# Mako_DSP_Power_R2_0.net
KiCad netlist of a schematic drawn in Altium Designer
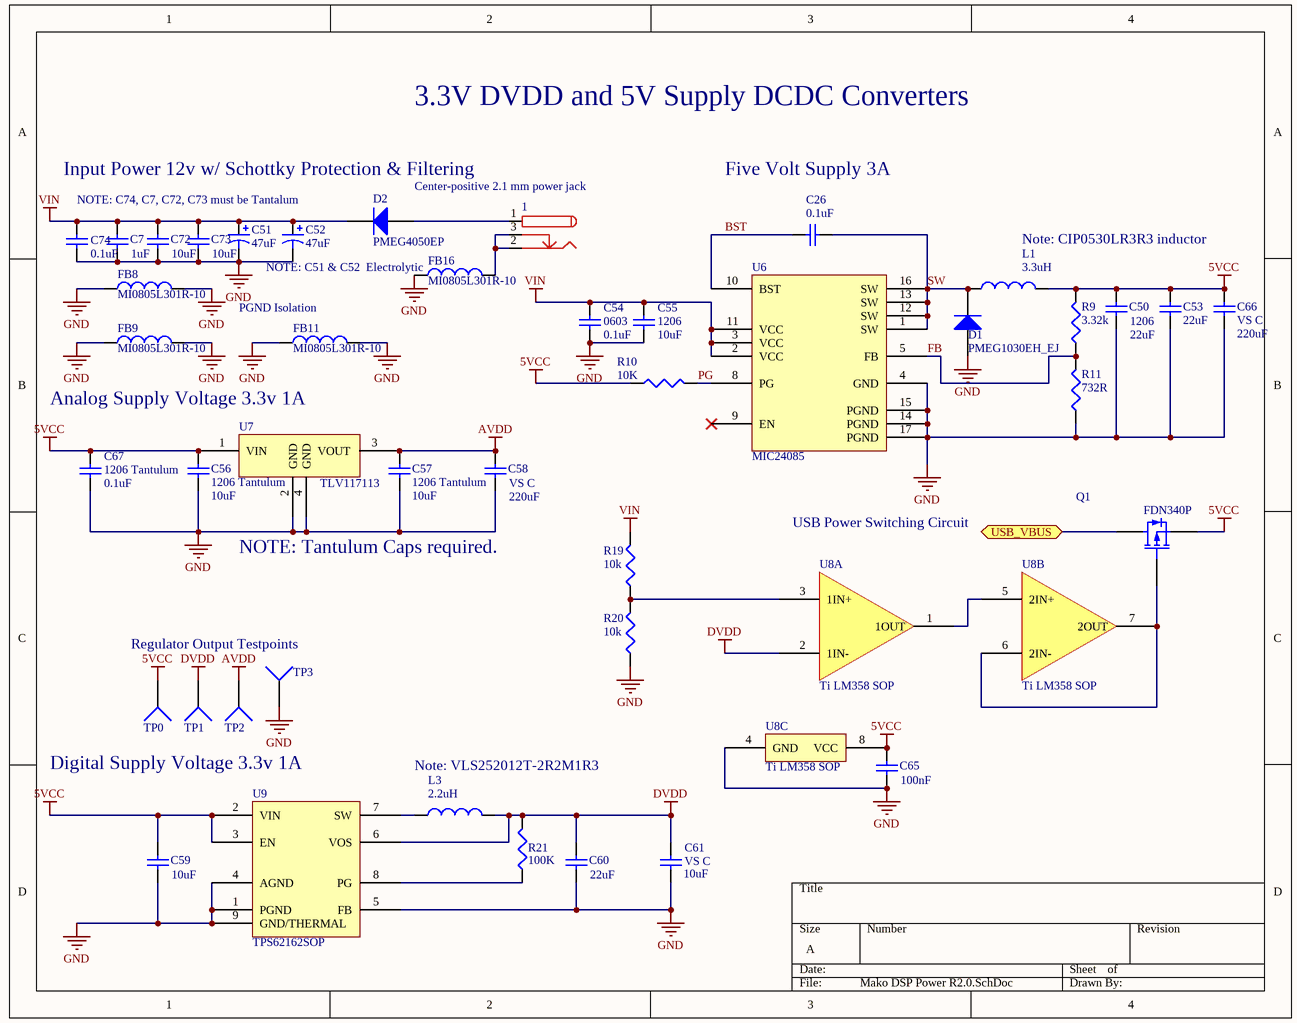
[diagram p0: Mako DSP Power R2.0.SchDoc]

(export (version "E")
  (design (tool "Eeschema 10.0.6"))
  (components
    (comp (ref "1")
      (value "Center-positive 2.1 mm power jack")
      (footprint "PJ-102AH")
      (description "Power jack")
      (fields (field (name "PUBLISHER") "Altium Limited"))
      (libsource (lib "Rascal") (part "PWR2.5"))
    )
    (comp (ref "C7")
      (value "1uF")
      (footprint "C1206")
      (description "Capacitor (Semiconductor SIM Model)")
      (fields (field (name "Comment") "Cap Semi") (field (name "PUBLISHER") "Altium Limited"))
      (libsource (lib "Miscellaneous Devices") (part "Cap Semi"))
    )
    (comp (ref "C26")
      (value "0.1uF")
      (footprint "1608[0603]")
      (description "Capacitor (Semiconductor SIM Model)")
      (fields (field (name "Comment") "Cap Semi") (field (name "PUBLISHER") "Altium Limited"))
      (libsource (lib "Miscellaneous Devices") (part "Cap Semi"))
    )
    (comp (ref "C50")
      (value "1206")
      (footprint "C1206")
      (description "Capacitor (Semiconductor SIM Model)")
      (fields (field (name "ALTIUM_VALUE") "22uF") (field (name "PUBLISHER") "Altium Limited"))
      (libsource (lib "Miscellaneous Devices") (part "Cap Semi"))
    )
    (comp (ref "C51")
      (value "47uF")
      (footprint "CAPPR2.5-6.3x5")
      (description "Polarized Capacitor (Radial)")
      (fields (field (name "Comment") "Cap Pol1") (field (name "PUBLISHER") "Altium Limited"))
      (libsource (lib "Miscellaneous Devices") (part "Cap Pol1"))
    )
    (comp (ref "C52")
      (value "47uF")
      (footprint "CAPPR2.5-6.3x5")
      (description "Polarized Capacitor (Radial)")
      (fields (field (name "Comment") "Cap Pol1") (field (name "PUBLISHER") "Altium Limited"))
      (libsource (lib "Miscellaneous Devices") (part "Cap Pol1"))
    )
    (comp (ref "C53")
      (value "22uF")
      (footprint "C1206")
      (description "Capacitor (Semiconductor SIM Model)")
      (fields (field (name "Comment") "Cap Semi") (field (name "PUBLISHER") "Altium Limited"))
      (libsource (lib "Miscellaneous Devices") (part "Cap Semi"))
    )
    (comp (ref "C54")
      (value "0603")
      (footprint "1608[0603]")
      (description "Capacitor (Semiconductor SIM Model)")
      (fields (field (name "ALTIUM_VALUE") "0.1uF") (field (name "PUBLISHER") "Altium Limited"))
      (libsource (lib "Miscellaneous Devices") (part "Cap Semi"))
    )
    (comp (ref "C55")
      (value "1206")
      (footprint "C1206")
      (description "Capacitor (Semiconductor SIM Model)")
      (fields (field (name "ALTIUM_VALUE") "10uF") (field (name "PUBLISHER") "Altium Limited"))
      (libsource (lib "Miscellaneous Devices") (part "Cap Semi"))
    )
    (comp (ref "C56")
      (value "1206 Tantulum")
      (footprint "C1206")
      (description "Capacitor (Semiconductor SIM Model)")
      (fields (field (name "ALTIUM_VALUE") "10uF") (field (name "PUBLISHER") "Altium Limited"))
      (libsource (lib "Miscellaneous Devices") (part "Cap Semi"))
    )
    (comp (ref "C57")
      (value "1206 Tantulum")
      (footprint "C1206")
      (description "Capacitor (Semiconductor SIM Model)")
      (fields (field (name "ALTIUM_VALUE") "10uF") (field (name "PUBLISHER") "Altium Limited"))
      (libsource (lib "Miscellaneous Devices") (part "Cap Semi"))
    )
    (comp (ref "C58")
      (value "VS C")
      (footprint "Panasonic VS C")
      (description "Capacitor (Semiconductor SIM Model)")
      (fields (field (name "ALTIUM_VALUE") "220uF") (field (name "PUBLISHER") "Altium Limited"))
      (libsource (lib "Miscellaneous Devices") (part "Cap Semi"))
    )
    (comp (ref "C59")
      (value "10uF")
      (footprint "C1206")
      (description "Capacitor (Semiconductor SIM Model)")
      (fields (field (name "Comment") "Cap Semi") (field (name "PUBLISHER") "Altium Limited"))
      (libsource (lib "Miscellaneous Devices") (part "Cap Semi"))
    )
    (comp (ref "C60")
      (value "22uF")
      (footprint "C1206")
      (description "Capacitor (Semiconductor SIM Model)")
      (fields (field (name "Comment") "Cap Semi") (field (name "PUBLISHER") "Altium Limited"))
      (libsource (lib "Miscellaneous Devices") (part "Cap Semi"))
    )
    (comp (ref "C61")
      (value "VS C")
      (footprint "Panasonic VS C")
      (description "Capacitor (Semiconductor SIM Model)")
      (fields (field (name "ALTIUM_VALUE") "10uF") (field (name "PUBLISHER") "Altium Limited"))
      (libsource (lib "Miscellaneous Devices") (part "Cap Semi"))
    )
    (comp (ref "C65")
      (value "100nF")
      (footprint "1608[0603]")
      (description "Capacitor (Semiconductor SIM Model)")
      (fields (field (name "Comment") "Cap Semi") (field (name "PUBLISHER") "Altium Limited"))
      (libsource (lib "Miscellaneous Devices") (part "Cap Semi"))
    )
    (comp (ref "C66")
      (value "VS C")
      (footprint "Panasonic VS C")
      (description "Capacitor (Semiconductor SIM Model)")
      (fields (field (name "ALTIUM_VALUE") "220uF") (field (name "PUBLISHER") "Altium Limited"))
      (libsource (lib "Miscellaneous Devices") (part "Cap Semi"))
    )
    (comp (ref "C67")
      (value "1206 Tantulum")
      (footprint "C1206")
      (description "Capacitor (Semiconductor SIM Model)")
      (fields (field (name "ALTIUM_VALUE") "0.1uF") (field (name "PUBLISHER") "Altium Limited"))
      (libsource (lib "Miscellaneous Devices") (part "Cap Semi"))
    )
    (comp (ref "C72")
      (value "10uF")
      (footprint "C1206")
      (description "Capacitor (Semiconductor SIM Model)")
      (fields (field (name "Comment") "Cap Semi") (field (name "PUBLISHER") "Altium Limited"))
      (libsource (lib "Miscellaneous Devices") (part "Cap Semi"))
    )
    (comp (ref "C73")
      (value "10uF")
      (footprint "C1206")
      (description "Capacitor (Semiconductor SIM Model)")
      (fields (field (name "Comment") "Cap Semi") (field (name "PUBLISHER") "Altium Limited"))
      (libsource (lib "Miscellaneous Devices") (part "Cap Semi"))
    )
    (comp (ref "C74")
      (value "0.1uF")
      (footprint "C1206")
      (description "Capacitor (Semiconductor SIM Model)")
      (fields (field (name "Comment") "Cap Semi") (field (name "PUBLISHER") "Altium Limited"))
      (libsource (lib "Miscellaneous Devices") (part "Cap Semi"))
    )
    (comp (ref "D1")
      (value "PMEG1030EH_EJ")
      (footprint "PMEG1030EH_EJ")
      (description "Default Diode")
      (fields (field (name "PUBLISHER") "Altium Limited"))
      (libsource (lib "") (part "Diode_1"))
    )
    (comp (ref "D2")
      (value "PMEG4050EP")
      (footprint "PMEG4050EP")
      (description "Default Diode")
      (fields (field (name "PUBLISHER") "Altium Limited"))
      (libsource (lib "Miscellaneous Devices") (part "Diode"))
    )
    (comp (ref "FB8")
      (value "MI0805L301R-10")
      (footprint "SM 0805 - gap trimmed")
      (description "Inductor")
      (fields (field (name "PUBLISHER") "Altium Limited"))
      (libsource (lib "Miscellaneous Devices") (part "Inductor"))
    )
    (comp (ref "FB9")
      (value "MI0805L301R-10")
      (footprint "SM 0805 - gap trimmed")
      (description "Inductor")
      (fields (field (name "PUBLISHER") "Altium Limited"))
      (libsource (lib "Miscellaneous Devices") (part "Inductor"))
    )
    (comp (ref "FB11")
      (value "MI0805L301R-10")
      (footprint "SM 0805 - gap trimmed")
      (description "Inductor")
      (fields (field (name "PUBLISHER") "Altium Limited"))
      (libsource (lib "Miscellaneous Devices") (part "Inductor"))
    )
    (comp (ref "FB16")
      (value "MI0805L301R-10")
      (footprint "SM 0805 - gap trimmed")
      (description "Inductor")
      (fields (field (name "PUBLISHER") "Altium Limited"))
      (libsource (lib "Miscellaneous Devices") (part "Inductor"))
    )
    (comp (ref "L1")
      (value "3.3uH")
      (footprint "CIP0530LR3R3")
      (description "Inductor")
      (fields (field (name "PUBLISHER") "Altium Limited"))
      (libsource (lib "Miscellaneous Devices") (part "Inductor"))
    )
    (comp (ref "L3")
      (value "2.2uH")
      (footprint "VLS252012T-2R2M1R3")
      (description "Inductor")
      (fields (field (name "PUBLISHER") "Altium Limited"))
      (libsource (lib "Miscellaneous Devices") (part "Inductor"))
    )
    (comp (ref "Q1")
      (value "FDN340P")
      (footprint "SOT23-3N")
      (description "P-Channel MOSFET")
      (fields (field (name "PUBLISHER") "Altium Limited"))
      (libsource (lib "Mako DSP Schematic Library") (part "FDN340P"))
    )
    (comp (ref "R9")
      (value "3.32k")
      (footprint "J1-0603")
      (description "Resistor")
      (fields (field (name "Comment") "Res3") (field (name "PUBLISHER") "Altium Limited"))
      (libsource (lib "Miscellaneous Devices") (part "Res3"))
    )
    (comp (ref "R10")
      (value "10K")
      (footprint "J1-0603")
      (description "Resistor")
      (fields (field (name "Comment") "Res3") (field (name "PUBLISHER") "Altium Limited"))
      (libsource (lib "Miscellaneous Devices") (part "Res3"))
    )
    (comp (ref "R11")
      (value "732R")
      (footprint "J1-0603")
      (description "Resistor")
      (fields (field (name "Comment") "Res3") (field (name "PUBLISHER") "Altium Limited"))
      (libsource (lib "Miscellaneous Devices") (part "Res3"))
    )
    (comp (ref "R19")
      (value "10k")
      (footprint "J1-0603")
      (description "Resistor")
      (fields (field (name "Comment") "Res3") (field (name "PUBLISHER") "Altium Limited"))
      (libsource (lib "Miscellaneous Devices") (part "Res3"))
    )
    (comp (ref "R20")
      (value "10k")
      (footprint "J1-0603")
      (description "Resistor")
      (fields (field (name "Comment") "Res3") (field (name "PUBLISHER") "Altium Limited"))
      (libsource (lib "Miscellaneous Devices") (part "Res3"))
    )
    (comp (ref "R21")
      (value "100K")
      (footprint "RESC2012L")
      (description "Resistor")
      (fields (field (name "Comment") "Res3") (field (name "PUBLISHER") "Altium Limited"))
      (libsource (lib "Miscellaneous Devices") (part "Res3"))
    )
    (comp (ref "TP0")
      (value "Socket")
      (footprint "PIN1")
      (fields (field (name "PUBLISHER") "Altium Limited"))
      (libsource (lib "Miscellaneous Connectors") (part "Socket"))
    )
    (comp (ref "TP1")
      (value "Socket")
      (footprint "PIN1")
      (fields (field (name "PUBLISHER") "Altium Limited"))
      (libsource (lib "Miscellaneous Connectors") (part "Socket"))
    )
    (comp (ref "TP2")
      (value "Socket")
      (footprint "PIN1")
      (fields (field (name "PUBLISHER") "Altium Limited"))
      (libsource (lib "Miscellaneous Connectors") (part "Socket"))
    )
    (comp (ref "TP3")
      (value "Socket")
      (footprint "PIN1")
      (fields (field (name "PUBLISHER") "Altium Limited"))
      (libsource (lib "Miscellaneous Connectors") (part "Socket"))
    )
    (comp (ref "U6")
      (value "MIC24085")
      (footprint "MIC24085-AYML")
      (libsource (lib "Adams Altium Library") (part "MIC24085"))
    )
    (comp (ref "U7")
      (value "TLV117113")
      (footprint "TLV117112")
      (description "Linear Regulator")
      (libsource (lib "Adams Altium Library") (part "TLV117112"))
    )
    (comp (ref "U8")
      (value "Ti LM358 SOP")
      (footprint "LM358")
      (libsource (lib "Mako DSP Schematic Library") (part "LM358_Symbol"))
    )
    (comp (ref "U9")
      (value "TPS62162SOP")
      (footprint "TPS62162SOP")
      (libsource (lib "Adams Altium Library") (part "TPS62162SOP"))
    )
  )
  (nets
    (net (code "1") (name "/BST") (class "Default")
      (node (ref "C26") (pin "2") (pinfunction "2_2") (pintype "passive"))
      (node (ref "U6") (pin "10") (pinfunction "BST_10") (pintype "passive"))
    )
    (net (code "2") (name "/FB") (class "Default")
      (node (ref "R11") (pin "2") (pinfunction "2_2") (pintype "passive"))
      (node (ref "R9") (pin "1") (pinfunction "1_1") (pintype "passive"))
      (node (ref "U6") (pin "5") (pinfunction "FB_5") (pintype "passive"))
    )
    (net (code "3") (name "/PG") (class "Default")
      (node (ref "R10") (pin "2") (pinfunction "2_2") (pintype "passive"))
      (node (ref "U6") (pin "8") (pinfunction "PG_8") (pintype "passive"))
    )
    (net (code "4") (name "/SW") (class "Default")
      (node (ref "C26") (pin "1") (pinfunction "1_1") (pintype "passive"))
      (node (ref "D1") (pin "2") (pinfunction "K_2") (pintype "passive"))
      (node (ref "L1") (pin "1") (pinfunction "1_1") (pintype "passive"))
      (node (ref "U6") (pin "1") (pinfunction "SW_1") (pintype "passive"))
      (node (ref "U6") (pin "12") (pinfunction "SW_12") (pintype "passive"))
      (node (ref "U6") (pin "13") (pinfunction "SW_13") (pintype "passive"))
      (node (ref "U6") (pin "16") (pinfunction "SW_16") (pintype "passive"))
    )
    (net (code "5") (name "/USB_VBUS") (class "Default")
      (node (ref "Q1") (pin "3") (pinfunction "S_3") (pintype "passive"))
    )
    (net (code "6") (name "5VCC") (class "Default")
      (node (ref "C50") (pin "2") (pinfunction "2_2") (pintype "passive"))
      (node (ref "C53") (pin "1") (pinfunction "1_1") (pintype "passive"))
      (node (ref "C56") (pin "1") (pinfunction "1_1") (pintype "passive"))
      (node (ref "C59") (pin "2") (pinfunction "2_2") (pintype "passive"))
      (node (ref "C65") (pin "1") (pinfunction "1_1") (pintype "passive"))
      (node (ref "C66") (pin "2") (pinfunction "2_2") (pintype "passive"))
      (node (ref "C67") (pin "2") (pinfunction "2_2") (pintype "passive"))
      (node (ref "L1") (pin "2") (pinfunction "2_2") (pintype "passive"))
      (node (ref "Q1") (pin "2") (pinfunction "D_2") (pintype "passive"))
      (node (ref "R10") (pin "1") (pinfunction "1_1") (pintype "passive"))
      (node (ref "R9") (pin "2") (pinfunction "2_2") (pintype "passive"))
      (node (ref "TP0") (pin "1") (pinfunction "1_1") (pintype "passive"))
      (node (ref "U7") (pin "1") (pinfunction "VIN_1") (pintype "passive"))
      (node (ref "U8") (pin "8") (pinfunction "VCC_8") (pintype "passive"))
      (node (ref "U9") (pin "2") (pinfunction "VIN_2") (pintype "passive"))
      (node (ref "U9") (pin "3") (pinfunction "EN_3") (pintype "passive"))
    )
    (net (code "7") (name "AVDD") (class "Default")
      (node (ref "C57") (pin "1") (pinfunction "1_1") (pintype "passive"))
      (node (ref "C58") (pin "1") (pinfunction "1_1") (pintype "passive"))
      (node (ref "TP2") (pin "1") (pinfunction "1_1") (pintype "passive"))
      (node (ref "U7") (pin "3") (pinfunction "VOUT_3") (pintype "passive"))
    )
    (net (code "8") (name "DVDD") (class "Default")
      (node (ref "C60") (pin "2") (pinfunction "2_2") (pintype "passive"))
      (node (ref "C61") (pin "1") (pinfunction "1_1") (pintype "passive"))
      (node (ref "L3") (pin "2") (pinfunction "2_2") (pintype "passive"))
      (node (ref "R21") (pin "2") (pinfunction "2_2") (pintype "passive"))
      (node (ref "TP1") (pin "1") (pinfunction "1_1") (pintype "passive"))
      (node (ref "U8") (pin "2") (pinfunction "1IN-_2") (pintype "passive"))
      (node (ref "U9") (pin "6") (pinfunction "VOS_6") (pintype "passive"))
    )
    (net (code "9") (name "GND") (class "Default")
      (node (ref "C50") (pin "1") (pinfunction "1_1") (pintype "passive"))
      (node (ref "C51") (pin "2") (pinfunction "2_2") (pintype "passive"))
      (node (ref "C52") (pin "2") (pinfunction "2_2") (pintype "passive"))
      (node (ref "C53") (pin "2") (pinfunction "2_2") (pintype "passive"))
      (node (ref "C54") (pin "1") (pinfunction "1_1") (pintype "passive"))
      (node (ref "C55") (pin "1") (pinfunction "1_1") (pintype "passive"))
      (node (ref "C56") (pin "2") (pinfunction "2_2") (pintype "passive"))
      (node (ref "C57") (pin "2") (pinfunction "2_2") (pintype "passive"))
      (node (ref "C58") (pin "2") (pinfunction "2_2") (pintype "passive"))
      (node (ref "C59") (pin "1") (pinfunction "1_1") (pintype "passive"))
      (node (ref "C60") (pin "1") (pinfunction "1_1") (pintype "passive"))
      (node (ref "C61") (pin "2") (pinfunction "2_2") (pintype "passive"))
      (node (ref "C65") (pin "2") (pinfunction "2_2") (pintype "passive"))
      (node (ref "C66") (pin "1") (pinfunction "1_1") (pintype "passive"))
      (node (ref "C67") (pin "1") (pinfunction "1_1") (pintype "passive"))
      (node (ref "C7") (pin "1") (pinfunction "1_1") (pintype "passive"))
      (node (ref "C72") (pin "1") (pinfunction "1_1") (pintype "passive"))
      (node (ref "C73") (pin "1") (pinfunction "1_1") (pintype "passive"))
      (node (ref "C74") (pin "1") (pinfunction "1_1") (pintype "passive"))
      (node (ref "D1") (pin "1") (pinfunction "A_1") (pintype "passive"))
      (node (ref "FB11") (pin "1") (pinfunction "1_1") (pintype "passive"))
      (node (ref "FB11") (pin "2") (pinfunction "2_2") (pintype "passive"))
      (node (ref "FB16") (pin "1") (pinfunction "1_1") (pintype "passive"))
      (node (ref "FB8") (pin "1") (pinfunction "1_1") (pintype "passive"))
      (node (ref "FB8") (pin "2") (pinfunction "2_2") (pintype "passive"))
      (node (ref "FB9") (pin "1") (pinfunction "1_1") (pintype "passive"))
      (node (ref "FB9") (pin "2") (pinfunction "2_2") (pintype "passive"))
      (node (ref "R11") (pin "1") (pinfunction "1_1") (pintype "passive"))
      (node (ref "R20") (pin "1") (pinfunction "1_1") (pintype "passive"))
      (node (ref "TP3") (pin "1") (pinfunction "1_1") (pintype "passive"))
      (node (ref "U6") (pin "14") (pinfunction "PGND_14") (pintype "passive"))
      (node (ref "U6") (pin "15") (pinfunction "PGND_15") (pintype "passive"))
      (node (ref "U6") (pin "17") (pinfunction "PGND_17") (pintype "passive"))
      (node (ref "U6") (pin "4") (pinfunction "GND_4") (pintype "passive"))
      (node (ref "U7") (pin "2") (pinfunction "GND_2") (pintype "passive"))
      (node (ref "U7") (pin "4") (pinfunction "GND_4") (pintype "passive"))
      (node (ref "U8") (pin "4") (pinfunction "GND_4") (pintype "passive"))
      (node (ref "U9") (pin "1") (pinfunction "PGND_1") (pintype "passive"))
      (node (ref "U9") (pin "4") (pinfunction "AGND_4") (pintype "passive"))
      (node (ref "U9") (pin "5") (pinfunction "FB_5") (pintype "passive"))
      (node (ref "U9") (pin "9") (pinfunction "GND/THERMAL_9") (pintype "passive"))
    )
    (net (code "10") (name "Net-(1-Pad2)") (class "Default")
      (node (ref "1") (pin "2") (pinfunction "2_2") (pintype "power_in"))
      (node (ref "1") (pin "3") (pinfunction "3_3") (pintype "power_in"))
      (node (ref "FB16") (pin "2") (pinfunction "2_2") (pintype "passive"))
    )
    (net (code "11") (name "Net-(D2-K)") (class "Default")
      (node (ref "1") (pin "1") (pinfunction "1_1") (pintype "power_in"))
      (node (ref "D2") (pin "2") (pinfunction "K_2") (pintype "passive"))
    )
    (net (code "12") (name "Net-(Q1-G)") (class "Default")
      (node (ref "Q1") (pin "1") (pinfunction "G_1") (pintype "passive"))
      (node (ref "U8") (pin "6") (pinfunction "2IN-_6") (pintype "passive"))
      (node (ref "U8") (pin "7") (pinfunction "2OUT_7") (pintype "passive"))
    )
    (net (code "13") (name "Net-(U8A-1IN+)") (class "Default")
      (node (ref "R19") (pin "1") (pinfunction "1_1") (pintype "passive"))
      (node (ref "R20") (pin "2") (pinfunction "2_2") (pintype "passive"))
      (node (ref "U8") (pin "3") (pinfunction "1IN+_3") (pintype "passive"))
    )
    (net (code "14") (name "Net-(U8A-1OUT)") (class "Default")
      (node (ref "U8") (pin "1") (pinfunction "1OUT_1") (pintype "passive"))
      (node (ref "U8") (pin "5") (pinfunction "2IN+_5") (pintype "passive"))
    )
    (net (code "15") (name "Net-(U9-PG)") (class "Default")
      (node (ref "R21") (pin "1") (pinfunction "1_1") (pintype "passive"))
      (node (ref "U9") (pin "8") (pinfunction "PG_8") (pintype "passive"))
    )
    (net (code "16") (name "Net-(U9-SW)") (class "Default")
      (node (ref "L3") (pin "1") (pinfunction "1_1") (pintype "passive"))
      (node (ref "U9") (pin "7") (pinfunction "SW_7") (pintype "passive"))
    )
    (net (code "17") (name "VIN") (class "Default")
      (node (ref "C51") (pin "1") (pinfunction "1_1") (pintype "passive"))
      (node (ref "C52") (pin "1") (pinfunction "1_1") (pintype "passive"))
      (node (ref "C54") (pin "2") (pinfunction "2_2") (pintype "passive"))
      (node (ref "C55") (pin "2") (pinfunction "2_2") (pintype "passive"))
      (node (ref "C7") (pin "2") (pinfunction "2_2") (pintype "passive"))
      (node (ref "C72") (pin "2") (pinfunction "2_2") (pintype "passive"))
      (node (ref "C73") (pin "2") (pinfunction "2_2") (pintype "passive"))
      (node (ref "C74") (pin "2") (pinfunction "2_2") (pintype "passive"))
      (node (ref "D2") (pin "1") (pinfunction "A_1") (pintype "passive"))
      (node (ref "R19") (pin "2") (pinfunction "2_2") (pintype "passive"))
      (node (ref "U6") (pin "11") (pinfunction "VCC_11") (pintype "passive"))
      (node (ref "U6") (pin "2") (pinfunction "VCC_2") (pintype "passive"))
      (node (ref "U6") (pin "3") (pinfunction "VCC_3") (pintype "passive"))
    )
    (net (code "18") (name "unconnected-(U6-EN-Pad9)") (class "Default")
      (node (ref "U6") (pin "9") (pinfunction "EN_9") (pintype "passive+no_connect"))
    )
    (net (code "19") (name "unconnected-(U6-NC-Pad6)") (class "Default")
      (node (ref "U6") (pin "6") (pinfunction "NC_6") (pintype "passive"))
    )
    (net (code "20") (name "unconnected-(U6-NC-Pad7)") (class "Default")
      (node (ref "U6") (pin "7") (pinfunction "NC_7") (pintype "passive"))
    )
  )
)
